# Adafruit_Bluefruit_LE_nRF8001_v2.net
KiCad netlist of a schematic drawn in EAGLE
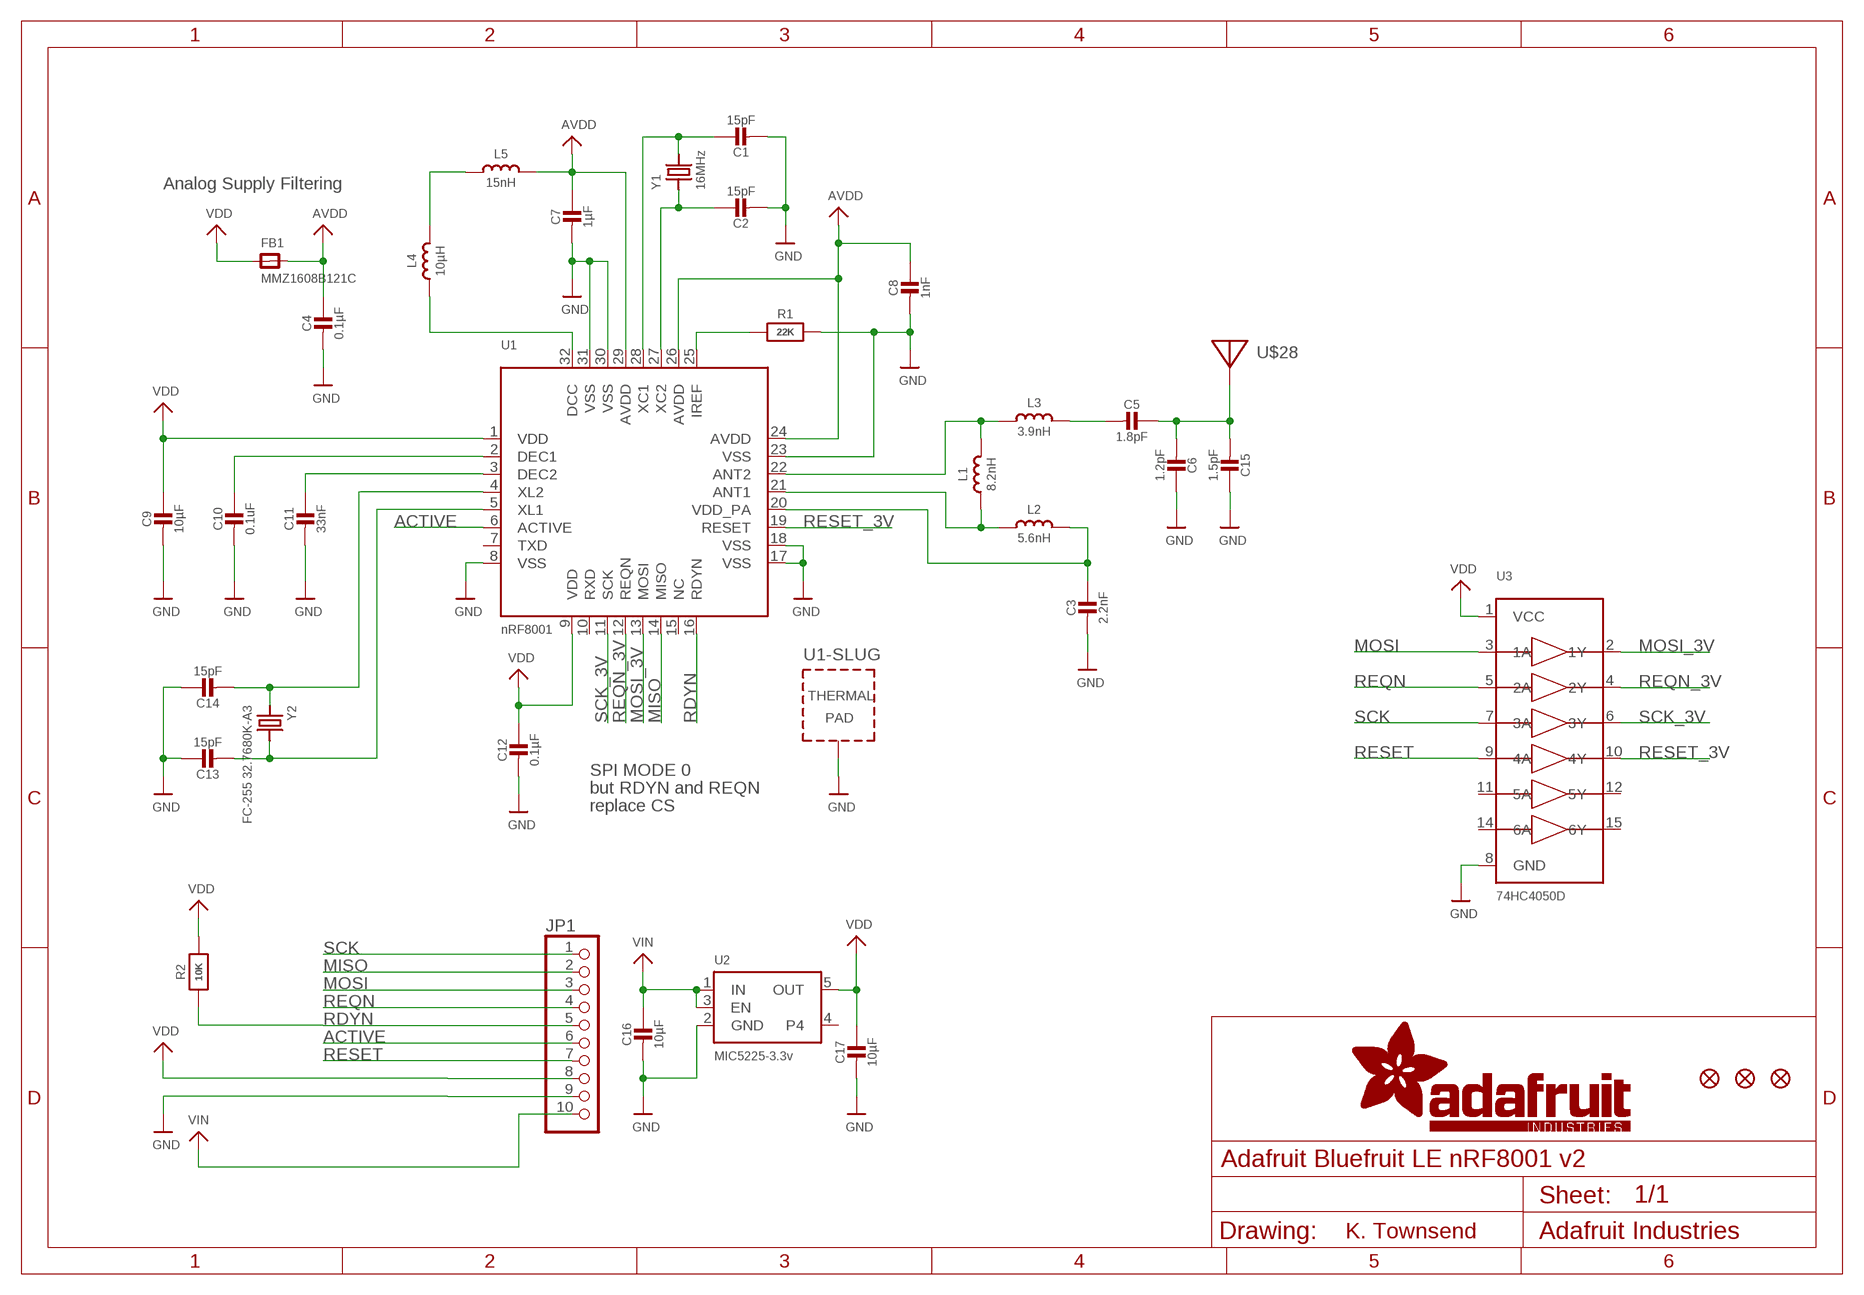
[diagram p0: schematic, sheet 1]

(export (version "E")
  (design (tool "Eeschema 10.0.6"))
  (components
    (comp (ref "C1")
      (value "15pF")
      (footprint "eagle-import:0805-NO")
      (libsource (lib "eagle-import") (part "CAP_CERAMIC0805-NOOUTLINE"))
    )
    (comp (ref "C2")
      (value "15pF")
      (footprint "eagle-import:0805-NO")
      (libsource (lib "eagle-import") (part "CAP_CERAMIC0805-NOOUTLINE"))
    )
    (comp (ref "C3")
      (value "2.2nF")
      (footprint "eagle-import:_0402")
      (libsource (lib "eagle-import") (part "CAP_CERAMIC_0402"))
    )
    (comp (ref "C4")
      (value "0.1µF")
      (footprint "eagle-import:0805-NO")
      (libsource (lib "eagle-import") (part "CAP_CERAMIC0805-NOOUTLINE"))
    )
    (comp (ref "C5")
      (value "1.8pF")
      (footprint "eagle-import:_0402MP")
      (libsource (lib "eagle-import") (part "CAP_CERAMIC_0402MP"))
    )
    (comp (ref "C6")
      (value "1.2pF")
      (footprint "eagle-import:_0402MP")
      (libsource (lib "eagle-import") (part "CAP_CERAMIC_0402MP"))
    )
    (comp (ref "C7")
      (value "1µF")
      (footprint "eagle-import:0805-NO")
      (libsource (lib "eagle-import") (part "CAP_CERAMIC0805-NOOUTLINE"))
    )
    (comp (ref "C8")
      (value "1nF")
      (footprint "eagle-import:_0603")
      (libsource (lib "eagle-import") (part "CAP_CERAMIC_0603"))
    )
    (comp (ref "C9")
      (value "10µF")
      (footprint "eagle-import:0805-NO")
      (libsource (lib "eagle-import") (part "CAP_CERAMIC0805-NOOUTLINE"))
    )
    (comp (ref "C10")
      (value "0.1uF")
      (footprint "eagle-import:0805-NO")
      (libsource (lib "eagle-import") (part "CAP_CERAMIC0805-NOOUTLINE"))
    )
    (comp (ref "C11")
      (value "33nF")
      (footprint "eagle-import:0805-NO")
      (libsource (lib "eagle-import") (part "CAP_CERAMIC0805-NOOUTLINE"))
    )
    (comp (ref "C12")
      (value "0.1µF")
      (footprint "eagle-import:0805-NO")
      (libsource (lib "eagle-import") (part "CAP_CERAMIC0805-NOOUTLINE"))
    )
    (comp (ref "C13")
      (value "15pF")
      (footprint "eagle-import:0805-NO")
      (libsource (lib "eagle-import") (part "CAP_CERAMIC0805-NOOUTLINE"))
    )
    (comp (ref "C14")
      (value "15pF")
      (footprint "eagle-import:0805-NO")
      (libsource (lib "eagle-import") (part "CAP_CERAMIC0805-NOOUTLINE"))
    )
    (comp (ref "C15")
      (value "1.5pF")
      (footprint "eagle-import:_0402MP")
      (libsource (lib "eagle-import") (part "CAP_CERAMIC_0402MP"))
    )
    (comp (ref "C16")
      (value "10µF")
      (footprint "eagle-import:0805-NO")
      (libsource (lib "eagle-import") (part "CAP_CERAMIC0805-NOOUTLINE"))
    )
    (comp (ref "C17")
      (value "10µF")
      (footprint "eagle-import:0805-NO")
      (libsource (lib "eagle-import") (part "CAP_CERAMIC0805-NOOUTLINE"))
    )
    (comp (ref "FB1")
      (value "MMZ1608B121C")
      (footprint "eagle-import:0805")
      (libsource (lib "eagle-import") (part "FERRITE0805"))
    )
    (comp (ref "FID1")
      (value "FIDUCIAL\"\"")
      (footprint "eagle-import:FIDUCIAL_1MM")
      (libsource (lib "eagle-import") (part "FIDUCIAL{dblquote}{dblquote}"))
    )
    (comp (ref "FID2")
      (value "FIDUCIAL\"\"")
      (footprint "eagle-import:FIDUCIAL_1MM")
      (libsource (lib "eagle-import") (part "FIDUCIAL{dblquote}{dblquote}"))
    )
    (comp (ref "FID3")
      (value "FIDUCIAL\"\"")
      (footprint "eagle-import:FIDUCIAL_1MM")
      (fields (field (name "BOM") "EXCLUDE"))
      (libsource (lib "eagle-import") (part "FIDUCIAL{dblquote}{dblquote}"))
    )
    (comp (ref "JP1")
      (value "HEADER-1X1070MIL")
      (footprint "eagle-import:1X10_ROUND70")
      (libsource (lib "eagle-import") (part "HEADER-1X1070MIL"))
    )
    (comp (ref "L1")
      (value "8.2nH")
      (footprint "eagle-import:_0402")
      (libsource (lib "eagle-import") (part "INDUCTOR_0402"))
    )
    (comp (ref "L2")
      (value "5.6nH")
      (footprint "eagle-import:_0402")
      (libsource (lib "eagle-import") (part "INDUCTOR_0402"))
    )
    (comp (ref "L3")
      (value "3.9nH")
      (footprint "eagle-import:_0402")
      (libsource (lib "eagle-import") (part "INDUCTOR_0402"))
    )
    (comp (ref "L4")
      (value "10µH")
      (footprint "eagle-import:_0603")
      (libsource (lib "eagle-import") (part "INDUCTOR_0603"))
    )
    (comp (ref "L5")
      (value "15nH")
      (footprint "eagle-import:_0603")
      (libsource (lib "eagle-import") (part "INDUCTOR_0603"))
    )
    (comp (ref "R1")
      (value "22K")
      (footprint "eagle-import:_0805MP")
      (libsource (lib "eagle-import") (part "RESISTOR_0805MP"))
    )
    (comp (ref "R2")
      (value "10K")
      (footprint "eagle-import:0805-NO")
      (libsource (lib "eagle-import") (part "RESISTOR0805_NOOUTLINE"))
    )
    (comp (ref "U$28")
      (value "ANTENNA_PCBNRF8001_1.6MM")
      (footprint "eagle-import:ANT_PCB_2.4GHZ_NRF8001_1.6MM_1OZ")
      (libsource (lib "eagle-import") (part "ANTENNA_PCBNRF8001_1.6MM"))
    )
    (comp (ref "U1")
      (value "nRF8001")
      (footprint "eagle-import:QFN32_5MM")
      (libsource (lib "eagle-import") (part "NRF8001"))
    )
    (comp (ref "U2")
      (value "MIC5225-3.3v")
      (footprint "eagle-import:SOT23-5")
      (libsource (lib "eagle-import") (part "VREG_SOT23-5"))
    )
    (comp (ref "U3")
      (value "74HC4050D")
      (footprint "eagle-import:TSSOP16")
      (libsource (lib "eagle-import") (part "74HC4050DTSSOP"))
    )
    (comp (ref "Y1")
      (value "16MHz")
      (footprint "eagle-import:CRYSTAL_3.2X2.5")
      (libsource (lib "eagle-import") (part "CRYSTAL3.2X2.5"))
    )
    (comp (ref "Y2")
      (value "FC-255 32.7680K-A3")
      (footprint "eagle-import:CRYSTAL_8X3.8")
      (libsource (lib "eagle-import") (part "CRYSTAL8.0X3.8"))
    )
  )
  (nets
    (net (code "1") (name "/ACTIVE") (class "Default")
      (node (ref "JP1") (pin "6") (pinfunction "6_6") (pintype "passive"))
      (node (ref "U1") (pin "6") (pinfunction "ACTIVE_6") (pintype "output"))
    )
    (net (code "2") (name "/MISO") (class "Default")
      (node (ref "JP1") (pin "2") (pinfunction "2_2") (pintype "passive"))
      (node (ref "U1") (pin "14") (pinfunction "MISO_14") (pintype "output"))
    )
    (net (code "3") (name "/MOSI") (class "Default")
      (node (ref "JP1") (pin "3") (pinfunction "3_3") (pintype "passive"))
      (node (ref "U3") (pin "3") (pinfunction "1A_3") (pintype "bidirectional"))
    )
    (net (code "4") (name "/MOSI_3V") (class "Default")
      (node (ref "U1") (pin "13") (pinfunction "MOSI_13") (pintype "input"))
      (node (ref "U3") (pin "2") (pinfunction "1Y_2") (pintype "bidirectional"))
    )
    (net (code "5") (name "/RDYN") (class "Default")
      (node (ref "JP1") (pin "5") (pinfunction "5_5") (pintype "passive"))
      (node (ref "R2") (pin "1") (pinfunction "1_1") (pintype "passive"))
      (node (ref "U1") (pin "16") (pinfunction "RDYN_16") (pintype "output"))
    )
    (net (code "6") (name "/REQN") (class "Default")
      (node (ref "JP1") (pin "4") (pinfunction "4_4") (pintype "passive"))
      (node (ref "U3") (pin "5") (pinfunction "2A_5") (pintype "bidirectional"))
    )
    (net (code "7") (name "/REQN_3V") (class "Default")
      (node (ref "U1") (pin "12") (pinfunction "REQN_12") (pintype "input"))
      (node (ref "U3") (pin "4") (pinfunction "2Y_4") (pintype "bidirectional"))
    )
    (net (code "8") (name "/RESET") (class "Default")
      (node (ref "JP1") (pin "7") (pinfunction "7_7") (pintype "passive"))
      (node (ref "U3") (pin "9") (pinfunction "4A_9") (pintype "bidirectional"))
    )
    (net (code "9") (name "/RESET_3V") (class "Default")
      (node (ref "U1") (pin "19") (pinfunction "RESET_19") (pintype "input"))
      (node (ref "U3") (pin "10") (pinfunction "4Y_10") (pintype "bidirectional"))
    )
    (net (code "10") (name "/SCK") (class "Default")
      (node (ref "JP1") (pin "1") (pinfunction "1_1") (pintype "passive"))
      (node (ref "U3") (pin "7") (pinfunction "3A_7") (pintype "bidirectional"))
    )
    (net (code "11") (name "/SCK_3V") (class "Default")
      (node (ref "U1") (pin "11") (pinfunction "SCK_11") (pintype "input"))
      (node (ref "U3") (pin "6") (pinfunction "3Y_6") (pintype "bidirectional"))
    )
    (net (code "12") (name "AVDD") (class "Default")
      (node (ref "C4") (pin "1") (pinfunction "1_1") (pintype "passive"))
      (node (ref "C7") (pin "1") (pinfunction "1_1") (pintype "passive"))
      (node (ref "C8") (pin "1") (pinfunction "1_1") (pintype "passive"))
      (node (ref "FB1") (pin "2") (pinfunction "P$2_2") (pintype "passive"))
      (node (ref "L5") (pin "2") (pinfunction "2_2") (pintype "passive"))
      (node (ref "U1") (pin "24") (pinfunction "AVDD_24") (pintype "power_in"))
      (node (ref "U1") (pin "26") (pinfunction "AVDD_26") (pintype "power_in"))
      (node (ref "U1") (pin "29") (pinfunction "AVDD_29") (pintype "power_in"))
    )
    (net (code "13") (name "GND") (class "Default")
      (node (ref "C1") (pin "2") (pinfunction "2_2") (pintype "passive"))
      (node (ref "C10") (pin "2") (pinfunction "2_2") (pintype "passive"))
      (node (ref "C11") (pin "2") (pinfunction "2_2") (pintype "passive"))
      (node (ref "C12") (pin "2") (pinfunction "2_2") (pintype "passive"))
      (node (ref "C13") (pin "1") (pinfunction "1_1") (pintype "passive"))
      (node (ref "C14") (pin "1") (pinfunction "1_1") (pintype "passive"))
      (node (ref "C15") (pin "1") (pinfunction "1_1") (pintype "passive"))
      (node (ref "C16") (pin "2") (pinfunction "2_2") (pintype "passive"))
      (node (ref "C17") (pin "2") (pinfunction "2_2") (pintype "passive"))
      (node (ref "C2") (pin "2") (pinfunction "2_2") (pintype "passive"))
      (node (ref "C3") (pin "2") (pinfunction "2_2") (pintype "passive"))
      (node (ref "C4") (pin "2") (pinfunction "2_2") (pintype "passive"))
      (node (ref "C6") (pin "1") (pinfunction "1_1") (pintype "passive"))
      (node (ref "C7") (pin "2") (pinfunction "2_2") (pintype "passive"))
      (node (ref "C8") (pin "2") (pinfunction "2_2") (pintype "passive"))
      (node (ref "C9") (pin "2") (pinfunction "2_2") (pintype "passive"))
      (node (ref "JP1") (pin "9") (pinfunction "9_9") (pintype "passive"))
      (node (ref "R1") (pin "2") (pinfunction "2_2") (pintype "passive"))
      (node (ref "U1") (pin "17") (pinfunction "VSS_17") (pintype "power_in"))
      (node (ref "U1") (pin "18") (pinfunction "VSS_18") (pintype "power_in"))
      (node (ref "U1") (pin "23") (pinfunction "VSS_23") (pintype "power_in"))
      (node (ref "U1") (pin "30") (pinfunction "VSS_30") (pintype "power_in"))
      (node (ref "U1") (pin "31") (pinfunction "VSS_31") (pintype "power_in"))
      (node (ref "U1") (pin "33") (pinfunction "TP_33") (pintype "power_in"))
      (node (ref "U1") (pin "8") (pinfunction "VSS_8") (pintype "power_in"))
      (node (ref "U2") (pin "2") (pinfunction "GND_2") (pintype "power_in"))
      (node (ref "U3") (pin "8") (pinfunction "GND_8") (pintype "bidirectional"))
    )
    (net (code "14") (name "Net-(C5-Pad2)") (class "Default")
      (node (ref "C5") (pin "2") (pinfunction "2_2") (pintype "passive"))
      (node (ref "L3") (pin "2") (pinfunction "2_2") (pintype "passive"))
    )
    (net (code "15") (name "Net-(L4-Pad2)") (class "Default")
      (node (ref "L4") (pin "2") (pinfunction "2_2") (pintype "passive"))
      (node (ref "L5") (pin "1") (pinfunction "1_1") (pintype "passive"))
    )
    (net (code "16") (name "Net-(U$28-P$1)") (class "Default")
      (node (ref "C15") (pin "2") (pinfunction "2_2") (pintype "passive"))
      (node (ref "C5") (pin "1") (pinfunction "1_1") (pintype "passive"))
      (node (ref "C6") (pin "2") (pinfunction "2_2") (pintype "passive"))
      (node (ref "U$28") (pin "FEED") (pinfunction "P$1_FEED") (pintype "passive"))
    )
    (net (code "17") (name "Net-(U1B-ANT1)") (class "Default")
      (node (ref "L1") (pin "1") (pinfunction "1_1") (pintype "passive"))
      (node (ref "L2") (pin "1") (pinfunction "1_1") (pintype "passive"))
      (node (ref "U1") (pin "21") (pinfunction "ANT1_21") (pintype "bidirectional"))
    )
    (net (code "18") (name "Net-(U1B-ANT2)") (class "Default")
      (node (ref "L1") (pin "2") (pinfunction "2_2") (pintype "passive"))
      (node (ref "L3") (pin "1") (pinfunction "1_1") (pintype "passive"))
      (node (ref "U1") (pin "22") (pinfunction "ANT2_22") (pintype "bidirectional"))
    )
    (net (code "19") (name "Net-(U1B-DCC)") (class "Default")
      (node (ref "L4") (pin "1") (pinfunction "1_1") (pintype "passive"))
      (node (ref "U1") (pin "32") (pinfunction "DCC_32") (pintype "bidirectional"))
    )
    (net (code "20") (name "Net-(U1B-DEC1)") (class "Default")
      (node (ref "C10") (pin "1") (pinfunction "1_1") (pintype "passive"))
      (node (ref "U1") (pin "2") (pinfunction "DEC1_2") (pintype "bidirectional"))
    )
    (net (code "21") (name "Net-(U1B-DEC2)") (class "Default")
      (node (ref "C11") (pin "1") (pinfunction "1_1") (pintype "passive"))
      (node (ref "U1") (pin "3") (pinfunction "DEC2_3") (pintype "bidirectional"))
    )
    (net (code "22") (name "Net-(U1B-IREF)") (class "Default")
      (node (ref "R1") (pin "1") (pinfunction "1_1") (pintype "passive"))
      (node (ref "U1") (pin "25") (pinfunction "IREF_25") (pintype "output"))
    )
    (net (code "23") (name "Net-(U1B-VDD_PA)") (class "Default")
      (node (ref "C3") (pin "1") (pinfunction "1_1") (pintype "passive"))
      (node (ref "L2") (pin "2") (pinfunction "2_2") (pintype "passive"))
      (node (ref "U1") (pin "20") (pinfunction "VDD_PA_20") (pintype "bidirectional"))
    )
    (net (code "24") (name "Net-(U1B-XC1)") (class "Default")
      (node (ref "C1") (pin "1") (pinfunction "1_1") (pintype "passive"))
      (node (ref "U1") (pin "28") (pinfunction "XC1_28") (pintype "input"))
      (node (ref "Y1") (pin "2") (pinfunction "2_2") (pintype "passive"))
    )
    (net (code "25") (name "Net-(U1B-XC2)") (class "Default")
      (node (ref "C2") (pin "1") (pinfunction "1_1") (pintype "passive"))
      (node (ref "U1") (pin "27") (pinfunction "XC2_27") (pintype "output"))
      (node (ref "Y1") (pin "1") (pinfunction "1_1") (pintype "passive"))
    )
    (net (code "26") (name "Net-(U1B-XL1)") (class "Default")
      (node (ref "C13") (pin "2") (pinfunction "2_2") (pintype "passive"))
      (node (ref "U1") (pin "5") (pinfunction "XL1_5") (pintype "input"))
      (node (ref "Y2") (pin "P$4") (pinfunction "2_P$4") (pintype "passive"))
    )
    (net (code "27") (name "Net-(U1B-XL2)") (class "Default")
      (node (ref "C14") (pin "2") (pinfunction "2_2") (pintype "passive"))
      (node (ref "U1") (pin "4") (pinfunction "XL2_4") (pintype "output"))
      (node (ref "Y2") (pin "P$1") (pinfunction "1_P$1") (pintype "passive"))
    )
    (net (code "28") (name "VDD") (class "Default")
      (node (ref "C12") (pin "1") (pinfunction "1_1") (pintype "passive"))
      (node (ref "C17") (pin "1") (pinfunction "1_1") (pintype "passive"))
      (node (ref "C9") (pin "1") (pinfunction "1_1") (pintype "passive"))
      (node (ref "FB1") (pin "1") (pinfunction "P$1_1") (pintype "passive"))
      (node (ref "JP1") (pin "8") (pinfunction "8_8") (pintype "passive"))
      (node (ref "R2") (pin "2") (pinfunction "2_2") (pintype "passive"))
      (node (ref "U1") (pin "1") (pinfunction "VDD_1") (pintype "power_in"))
      (node (ref "U1") (pin "9") (pinfunction "VDD_9") (pintype "power_in"))
      (node (ref "U2") (pin "5") (pinfunction "OUT_5") (pintype "power_in"))
      (node (ref "U3") (pin "1") (pinfunction "VCC_1") (pintype "bidirectional"))
    )
    (net (code "29") (name "VIN") (class "Default")
      (node (ref "C16") (pin "1") (pinfunction "1_1") (pintype "passive"))
      (node (ref "JP1") (pin "10") (pinfunction "10_10") (pintype "passive"))
      (node (ref "U2") (pin "1") (pinfunction "IN_1") (pintype "power_in"))
      (node (ref "U2") (pin "3") (pinfunction "EN_3") (pintype "input"))
    )
    (net (code "30") (name "unconnected-(U1B-NC-Pad15)") (class "Default")
      (node (ref "U1") (pin "15") (pinfunction "NC_15") (pintype "no_connect"))
    )
    (net (code "31") (name "unconnected-(U1B-RXD-Pad10)") (class "Default")
      (node (ref "U1") (pin "10") (pinfunction "RXD_10") (pintype "input"))
    )
    (net (code "32") (name "unconnected-(U1B-TXD-Pad7)") (class "Default")
      (node (ref "U1") (pin "7") (pinfunction "TXD_7") (pintype "output"))
    )
    (net (code "33") (name "unconnected-(U2-P4-Pad4)") (class "Default")
      (node (ref "U2") (pin "4") (pinfunction "P4_4") (pintype "bidirectional"))
    )
    (net (code "34") (name "unconnected-(U3-5A-Pad11)") (class "Default")
      (node (ref "U3") (pin "11") (pinfunction "5A_11") (pintype "bidirectional"))
    )
    (net (code "35") (name "unconnected-(U3-5Y-Pad12)") (class "Default")
      (node (ref "U3") (pin "12") (pinfunction "5Y_12") (pintype "bidirectional"))
    )
    (net (code "36") (name "unconnected-(U3-6A-Pad14)") (class "Default")
      (node (ref "U3") (pin "14") (pinfunction "6A_14") (pintype "bidirectional"))
    )
    (net (code "37") (name "unconnected-(U3-6Y-Pad15)") (class "Default")
      (node (ref "U3") (pin "15") (pinfunction "6Y_15") (pintype "bidirectional"))
    )
  )
)
